# Nrf2460_2.net
KiCad netlist of a schematic drawn in Altium Designer
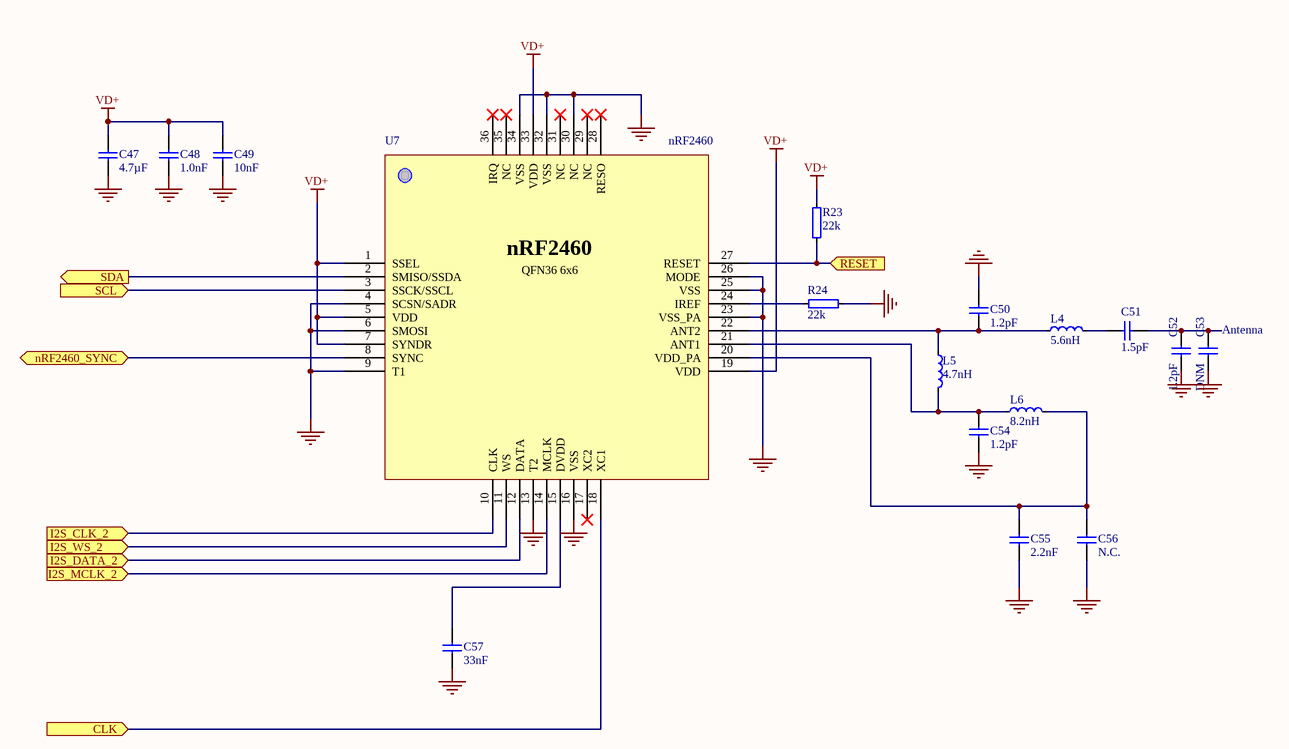
[diagram p0: Nrf2460_2.SchDoc]

(export (version "E")
  (design (tool "Eeschema 10.0.6"))
  (components
    (comp (ref "C47")
      (value "4.7µF")
      (footprint "0805")
      (description "Chip Cap 0805")
      (fields (field (name "PART NUMBER") "C0805-4µ7") (field (name "PUBLISHER") "Nordic Semiconductor"))
      (libsource (lib "Nordic Passive DB") (part "CAP"))
    )
    (comp (ref "C48")
      (value "1.0nF")
      (footprint "0402s")
      (description "Chip Cap 0402")
      (fields (field (name "PART NUMBER") "C0402-1n0") (field (name "PUBLISHER") "Nordic Semiconductor"))
      (libsource (lib "Nordic Passive DB") (part "CAP"))
    )
    (comp (ref "C49")
      (value "10nF")
      (footprint "0402s")
      (description "Chip Cap 0402")
      (fields (field (name "PART NUMBER") "C0402-10n") (field (name "PUBLISHER") "Nordic Semiconductor"))
      (libsource (lib "Nordic Passive DB") (part "CAP"))
    )
    (comp (ref "C50")
      (value "1.2pF")
      (footprint "0402s")
      (description "Chip Cap 0402")
      (fields (field (name "PART NUMBER") "C0402-1.2p") (field (name "PUBLISHER") "Nordic Semiconductor"))
      (libsource (lib "Nordic Passive DB") (part "CAP"))
    )
    (comp (ref "C51")
      (value "1.5pF")
      (footprint "0402s")
      (description "Chip Cap 0402")
      (fields (field (name "PART NUMBER") "C0402-1.5p") (field (name "PUBLISHER") "Nordic Semiconductor"))
      (libsource (lib "Nordic Passive DB") (part "CAP"))
    )
    (comp (ref "C52")
      (value "1.2pF")
      (footprint "0402s")
      (description "Chip Cap 0402")
      (fields (field (name "PART NUMBER") "C0402-1.2p") (field (name "PUBLISHER") "Nordic Semiconductor"))
      (libsource (lib "Nordic Passive DB") (part "CAP"))
    )
    (comp (ref "C53")
      (value "DNM")
      (footprint "0402s")
      (description "Chip Cap 0402")
      (fields (field (name "PART NUMBER") "C0402-1.2p") (field (name "PUBLISHER") "Nordic Semiconductor"))
      (libsource (lib "Nordic Passive DB") (part "CAP"))
    )
    (comp (ref "C54")
      (value "1.2pF")
      (footprint "0402s")
      (description "Chip Cap 0402")
      (fields (field (name "PART NUMBER") "C0402-1.2p") (field (name "PUBLISHER") "Nordic Semiconductor"))
      (libsource (lib "Nordic Passive DB") (part "CAP"))
    )
    (comp (ref "C55")
      (value "2.2nF")
      (footprint "0402s")
      (description "Chip Cap 0402")
      (fields (field (name "PART NUMBER") "C0402-2n2") (field (name "PUBLISHER") "Nordic Semiconductor"))
      (libsource (lib "Nordic Passive DB") (part "CAP"))
    )
    (comp (ref "C56")
      (value "N.C.")
      (footprint "0402s")
      (description "Chip Cap 0402")
      (fields (field (name "PART NUMBER") "C0402-N.C.") (field (name "PUBLISHER") "Nordic Semiconductor"))
      (libsource (lib "Nordic Passive DB") (part "CAP_NO_BOM"))
    )
    (comp (ref "C57")
      (value "33nF")
      (footprint "0402s")
      (description "Chip Cap 0402")
      (fields (field (name "PART NUMBER") "C0402-33n") (field (name "PUBLISHER") "Nordic Semiconductor"))
      (libsource (lib "Nordic Passive DB") (part "CAP"))
    )
    (comp (ref "L4")
      (value "5.6nH")
      (footprint "0402s")
      (description "Chip Ind 0402")
      (fields
        (field (name "PART NUMBER") "L0402-5n6")
        (field (name "MANUFACTURER") "Murata")
        (field (name "PUBLISHER") "Nordic Semiconductor")
      )
      (libsource (lib "Nordic Passive DB") (part "IND"))
    )
    (comp (ref "L5")
      (value "4.7nH")
      (footprint "0402s")
      (description "Chip Ind 0402")
      (fields
        (field (name "PART NUMBER") "L0402-4n7")
        (field (name "MANUFACTURER") "Murata")
        (field (name "PUBLISHER") "Nordic Semiconductor")
      )
      (libsource (lib "Nordic Passive DB") (part "IND"))
    )
    (comp (ref "L6")
      (value "8.2nH")
      (footprint "0402s")
      (description "Chip Ind 0402")
      (fields
        (field (name "PART NUMBER") "L0402-8n2")
        (field (name "MANUFACTURER") "Murata")
        (field (name "PUBLISHER") "Nordic Semiconductor")
      )
      (libsource (lib "Nordic Passive DB") (part "IND"))
    )
    (comp (ref "R23")
      (value "22k")
      (footprint "0402s")
      (description "Chip Res 0402")
      (fields (field (name "PART NUMBER") "R0402-22k") (field (name "PUBLISHER") "Nordic Semiconductor"))
      (libsource (lib "Nordic Passive DB") (part "RES_1"))
    )
    (comp (ref "R24")
      (value "22k")
      (footprint "0402s")
      (description "Chip Res 0402")
      (fields (field (name "PART NUMBER") "R0402-22k") (field (name "PUBLISHER") "Nordic Semiconductor"))
      (libsource (lib "Nordic Passive DB") (part "RES_1"))
    )
    (comp (ref "U7")
      (value "nRF2460")
      (footprint "Nordic_QFN36")
      (description "2.4GHz Single Chip Wireless Audio Streamer")
      (fields
        (field (name "MANUFACTURER") "Nordic Semiconductor")
        (field (name "PUBLISHER") "Nordic Semiconductor")
      )
      (libsource (lib "Nordic Active DB") (part "nRF2460"))
    )
  )
  (nets
    (net (code "1") (name "/CLK") (class "Default")
      (node (ref "U7") (pin "18") (pinfunction "XC1_18") (pintype "passive"))
    )
    (net (code "2") (name "/I2S_CLK_2") (class "Default")
      (node (ref "U7") (pin "10") (pinfunction "CLK_10") (pintype "passive"))
    )
    (net (code "3") (name "/I2S_DATA_2") (class "Default")
      (node (ref "U7") (pin "12") (pinfunction "DATA_12") (pintype "passive"))
    )
    (net (code "4") (name "/I2S_MCLK_2") (class "Default")
      (node (ref "U7") (pin "14") (pinfunction "MCLK_14") (pintype "passive"))
    )
    (net (code "5") (name "/I2S_WS_2") (class "Default")
      (node (ref "U7") (pin "11") (pinfunction "WS_11") (pintype "passive"))
    )
    (net (code "6") (name "/RESET") (class "Default")
      (node (ref "R23") (pin "1") (pinfunction "1_1") (pintype "passive"))
      (node (ref "U7") (pin "27") (pinfunction "RESET_27") (pintype "passive"))
    )
    (net (code "7") (name "/SCL") (class "Default")
      (node (ref "U7") (pin "3") (pinfunction "SSCK/SSCL_3") (pintype "passive"))
    )
    (net (code "8") (name "/SDA") (class "Default")
      (node (ref "U7") (pin "2") (pinfunction "SMISO/SSDA_2") (pintype "passive"))
    )
    (net (code "9") (name "/nRF2460_SYNC") (class "Default")
      (node (ref "U7") (pin "8") (pinfunction "SYNC_8") (pintype "passive"))
    )
    (net (code "10") (name "GND") (class "Default")
      (node (ref "C47") (pin "2") (pinfunction "2_2") (pintype "passive"))
      (node (ref "C48") (pin "2") (pinfunction "2_2") (pintype "passive"))
      (node (ref "C49") (pin "2") (pinfunction "2_2") (pintype "passive"))
      (node (ref "C50") (pin "2") (pinfunction "2_2") (pintype "passive"))
      (node (ref "C52") (pin "1") (pinfunction "1_1") (pintype "passive"))
      (node (ref "C53") (pin "1") (pinfunction "1_1") (pintype "passive"))
      (node (ref "C54") (pin "1") (pinfunction "1_1") (pintype "passive"))
      (node (ref "C55") (pin "1") (pinfunction "1_1") (pintype "passive"))
      (node (ref "C56") (pin "1") (pinfunction "1_1") (pintype "passive"))
      (node (ref "C57") (pin "1") (pinfunction "1_1") (pintype "passive"))
      (node (ref "R24") (pin "1") (pinfunction "1_1") (pintype "passive"))
      (node (ref "U7") (pin "13") (pinfunction "T2_13") (pintype "passive"))
      (node (ref "U7") (pin "16") (pinfunction "VSS_16") (pintype "passive"))
      (node (ref "U7") (pin "23") (pinfunction "VSS_PA_23") (pintype "passive"))
      (node (ref "U7") (pin "25") (pinfunction "VSS_25") (pintype "passive"))
      (node (ref "U7") (pin "26") (pinfunction "MODE_26") (pintype "passive"))
      (node (ref "U7") (pin "30") (pinfunction "NC_30") (pintype "passive"))
      (node (ref "U7") (pin "32") (pinfunction "VSS_32") (pintype "passive"))
      (node (ref "U7") (pin "34") (pinfunction "VSS_34") (pintype "passive"))
      (node (ref "U7") (pin "4") (pinfunction "SCSN/SADR_4") (pintype "passive"))
      (node (ref "U7") (pin "6") (pinfunction "SMOSI_6") (pintype "passive"))
      (node (ref "U7") (pin "9") (pinfunction "T1_9") (pintype "passive"))
    )
    (net (code "11") (name "Net-(C51-Pad1)") (class "Default")
      (node (ref "C51") (pin "1") (pinfunction "1_1") (pintype "passive"))
      (node (ref "C52") (pin "2") (pinfunction "2_2") (pintype "passive"))
      (node (ref "C53") (pin "2") (pinfunction "2_2") (pintype "passive"))
    )
    (net (code "12") (name "Net-(C51-Pad2)") (class "Default")
      (node (ref "C51") (pin "2") (pinfunction "2_2") (pintype "passive"))
      (node (ref "L4") (pin "2") (pinfunction "2_2") (pintype "passive"))
    )
    (net (code "13") (name "Net-(U7-ANT1)") (class "Default")
      (node (ref "C54") (pin "2") (pinfunction "2_2") (pintype "passive"))
      (node (ref "L5") (pin "2") (pinfunction "2_2") (pintype "passive"))
      (node (ref "L6") (pin "1") (pinfunction "1_1") (pintype "passive"))
      (node (ref "U7") (pin "21") (pinfunction "ANT1_21") (pintype "passive"))
    )
    (net (code "14") (name "Net-(U7-ANT2)") (class "Default")
      (node (ref "C50") (pin "1") (pinfunction "1_1") (pintype "passive"))
      (node (ref "L4") (pin "1") (pinfunction "1_1") (pintype "passive"))
      (node (ref "L5") (pin "1") (pinfunction "1_1") (pintype "passive"))
      (node (ref "U7") (pin "22") (pinfunction "ANT2_22") (pintype "passive"))
    )
    (net (code "15") (name "Net-(U7-DVDD)") (class "Default")
      (node (ref "C57") (pin "2") (pinfunction "2_2") (pintype "passive"))
      (node (ref "U7") (pin "15") (pinfunction "DVDD_15") (pintype "passive"))
    )
    (net (code "16") (name "Net-(U7-IREF)") (class "Default")
      (node (ref "R24") (pin "2") (pinfunction "2_2") (pintype "passive"))
      (node (ref "U7") (pin "24") (pinfunction "IREF_24") (pintype "passive"))
    )
    (net (code "17") (name "Net-(U7-VDD_PA)") (class "Default")
      (node (ref "C55") (pin "2") (pinfunction "2_2") (pintype "passive"))
      (node (ref "C56") (pin "2") (pinfunction "2_2") (pintype "passive"))
      (node (ref "L6") (pin "2") (pinfunction "2_2") (pintype "passive"))
      (node (ref "U7") (pin "20") (pinfunction "VDD_PA_20") (pintype "passive"))
    )
    (net (code "18") (name "VD+") (class "Default")
      (node (ref "C47") (pin "1") (pinfunction "1_1") (pintype "passive"))
      (node (ref "C48") (pin "1") (pinfunction "1_1") (pintype "passive"))
      (node (ref "C49") (pin "1") (pinfunction "1_1") (pintype "passive"))
      (node (ref "R23") (pin "2") (pinfunction "2_2") (pintype "passive"))
      (node (ref "U7") (pin "1") (pinfunction "SSEL_1") (pintype "passive"))
      (node (ref "U7") (pin "19") (pinfunction "VDD_19") (pintype "passive"))
      (node (ref "U7") (pin "33") (pinfunction "VDD_33") (pintype "passive"))
      (node (ref "U7") (pin "5") (pinfunction "VDD_5") (pintype "passive"))
      (node (ref "U7") (pin "7") (pinfunction "SYNDR_7") (pintype "passive"))
    )
    (net (code "19") (name "unconnected-(U7-IRQ-Pad36)") (class "Default")
      (node (ref "U7") (pin "36") (pinfunction "IRQ_36") (pintype "passive+no_connect"))
    )
    (net (code "20") (name "unconnected-(U7-NC-Pad29)") (class "Default")
      (node (ref "U7") (pin "29") (pinfunction "NC_29") (pintype "passive+no_connect"))
    )
    (net (code "21") (name "unconnected-(U7-NC-Pad31)") (class "Default")
      (node (ref "U7") (pin "31") (pinfunction "NC_31") (pintype "passive+no_connect"))
    )
    (net (code "22") (name "unconnected-(U7-NC-Pad35)") (class "Default")
      (node (ref "U7") (pin "35") (pinfunction "NC_35") (pintype "passive+no_connect"))
    )
    (net (code "23") (name "unconnected-(U7-RESO-Pad28)") (class "Default")
      (node (ref "U7") (pin "28") (pinfunction "RESO_28") (pintype "passive+no_connect"))
    )
    (net (code "24") (name "unconnected-(U7-XC2-Pad17)") (class "Default")
      (node (ref "U7") (pin "17") (pinfunction "XC2_17") (pintype "passive+no_connect"))
    )
  )
)
